# MINI-STM32.net
KiCad netlist of a schematic drawn in Altium Designer
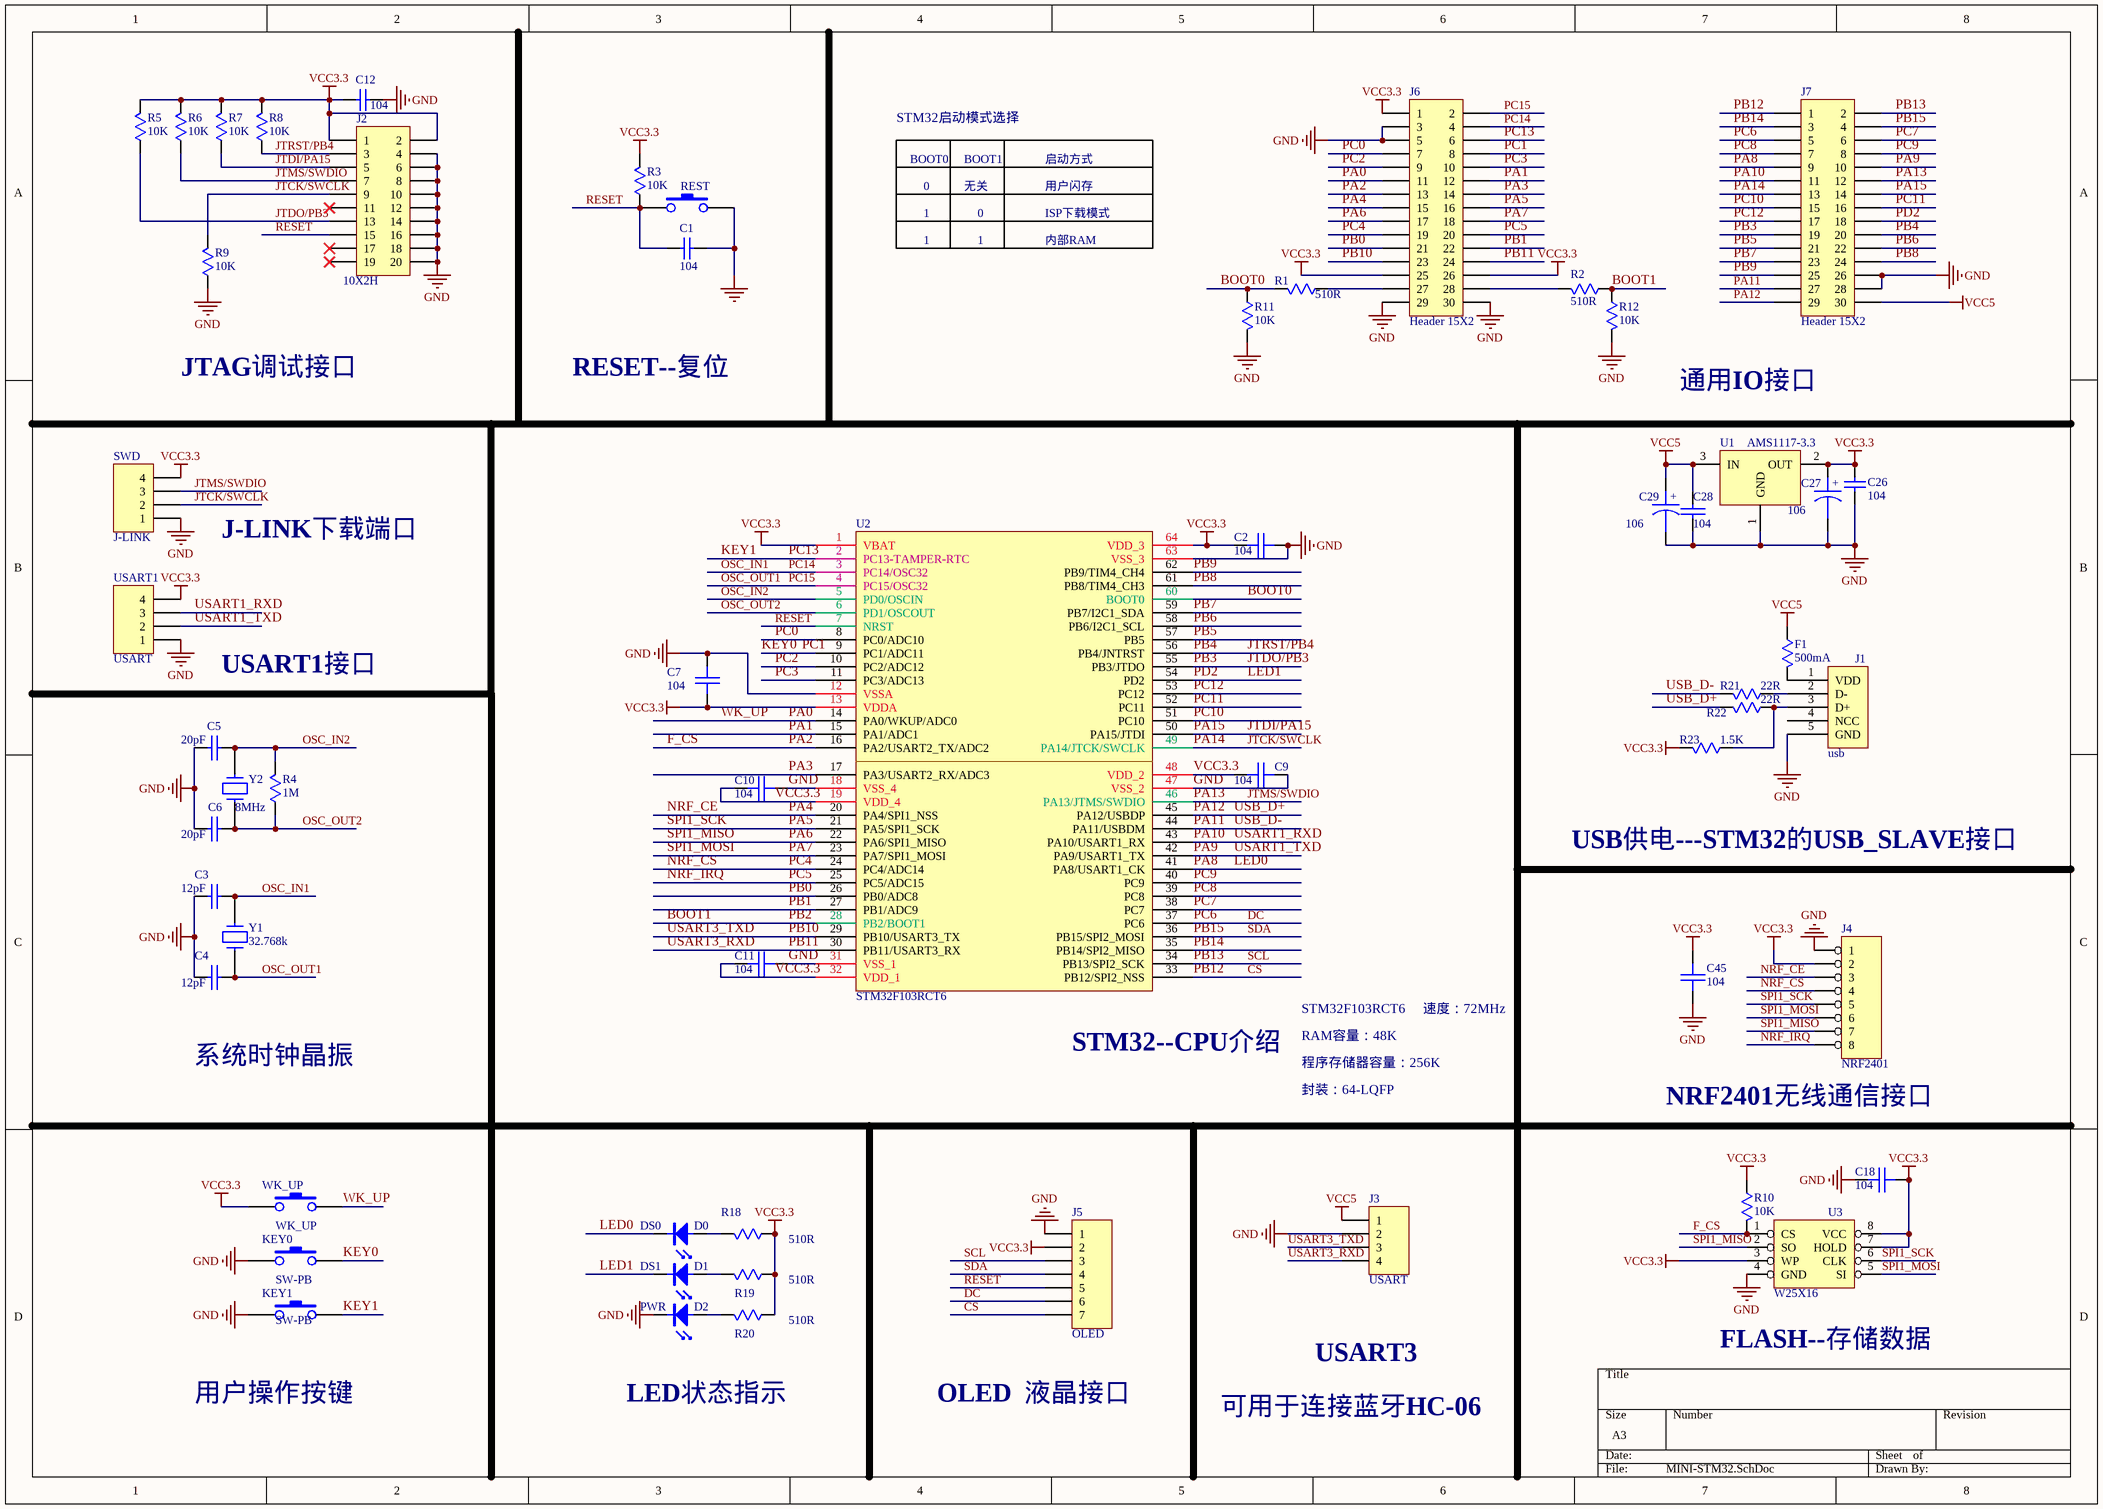
[diagram p0: MINI-STM32.SchDoc]

(export (version "E")
  (design (tool "Eeschema 10.0.6"))
  (components
    (comp (ref "C1")
      (value "104")
      (footprint "0603C")
      (description "GRM39 X7R102K50PT")
      (fields (field (name "PUBLISHER") "Altium Limited"))
      (libsource (lib "Miscellaneous Devices") (part "CAP"))
    )
    (comp (ref "C2") (value "104") (footprint "0603J") (libsource (lib "YT1_SCH_99SE") (part "CAP")))
    (comp (ref "C3")
      (value "12pF")
      (footprint "0603J")
      (description "CAP CHIP 20P 50V(+-5% C0G 0603)")
      (libsource (lib "") (part "CAP_1"))
    )
    (comp (ref "C4")
      (value "12pF")
      (footprint "0603J")
      (description "CAP CHIP 20P 50V(+-5% C0G 0603)")
      (libsource (lib "") (part "CAP_1"))
    )
    (comp (ref "C5")
      (value "20pF")
      (footprint "0603J")
      (description "CAP CHIP 20P 50V(+-5% C0G 0603)")
      (libsource (lib "") (part "CAP_1"))
    )
    (comp (ref "C6")
      (value "20pF")
      (footprint "0603J")
      (description "CAP CHIP 20P 50V(+-5% C0G 0603)")
      (libsource (lib "") (part "CAP_1"))
    )
    (comp (ref "C7") (value "104") (footprint "0603J") (libsource (lib "YT1_SCH_99SE") (part "CAP")))
    (comp (ref "C9") (value "104") (footprint "0603J") (libsource (lib "YT1_SCH_99SE") (part "CAP")))
    (comp (ref "C10") (value "104") (footprint "0603J") (libsource (lib "YT1_SCH_99SE") (part "CAP")))
    (comp (ref "C11") (value "104") (footprint "0603J") (libsource (lib "YT1_SCH_99SE") (part "CAP")))
    (comp (ref "C12")
      (value "104")
      (footprint "0603C")
      (description "GRM39 X7R102K50PT")
      (fields (field (name "PUBLISHER") "Altium Limited"))
      (libsource (lib "Miscellaneous Devices") (part "CAP"))
    )
    (comp (ref "C18") (value "104") (footprint "0603J") (libsource (lib "YT1_SCH_99SE") (part "CAP")))
    (comp (ref "C26")
      (value "104")
      (footprint "0603J")
      (description "Capacitor")
      (fields (field (name "PUBLISHER") "Altium Limited"))
      (libsource (lib "*") (part "Cap"))
    )
    (comp (ref "C27")
      (value "106")
      (footprint "TAC_3216")
      (description "Capacitor")
      (libsource (lib "*") (part "CAPACITOR POL"))
    )
    (comp (ref "C28")
      (value "104")
      (footprint "0603J")
      (description "Capacitor")
      (libsource (lib "*") (part "CAP"))
    )
    (comp (ref "C29")
      (value "106")
      (footprint "TAC_3216")
      (description "Capacitor")
      (libsource (lib "*") (part "CAPACITOR POL"))
    )
    (comp (ref "C45") (value "104") (footprint "0603J") (libsource (lib "YT1_SCH_99SE") (part "CAP")))
    (comp (ref "D0") (value "DS0") (footprint "LED_0603(B)") (libsource (lib "YT1_SCH_99SE") (part "LED")))
    (comp (ref "D1") (value "DS1") (footprint "LED_0603(B)") (libsource (lib "YT1_SCH_99SE") (part "LED")))
    (comp (ref "D2") (value "PWR") (footprint "LED_0603(B)") (libsource (lib "YT1_SCH_99SE") (part "LED")))
    (comp (ref "F1") (value "500mA") (footprint "RC0805") (libsource (lib "YT1_SCH_99SE") (part "RES")))
    (comp (ref "J1") (value "usb") (footprint "mini_USB") (libsource (lib "YT1_SCH_99SE") (part "usb")))
    (comp (ref "J2")
      (value "10X2H")
      (footprint "IDC20")
      (description "Header, 10-Pin, Dual row, Right Angle")
      (fields (field (name "PUBLISHER") "Altium Limited"))
      (libsource (lib "Miscellaneous Connectors") (part "Header 10X2H"))
    )
    (comp (ref "J3")
      (value "USART")
      (footprint "HDR1X4")
      (description "Header, 4-Pin")
      (fields (field (name "PUBLISHER") "Altium Limited"))
      (libsource (lib "") (part "Header 4_1"))
    )
    (comp (ref "J4")
      (value "NRF2401")
      (footprint "HDR2X4")
      (description "8 Pin Header")
      (libsource (lib "YT1_SCH_99SE") (part "HEADER 8"))
    )
    (comp (ref "J5")
      (value "OLED")
      (footprint "HDR1X7")
      (description "Header, 7-Pin")
      (fields (field (name "PUBLISHER") "Altium Limited"))
      (libsource (lib "Miscellaneous Connectors") (part "Header 7"))
    )
    (comp (ref "J6")
      (value "Header 15X2")
      (footprint "IDE15X2_2.54")
      (description "Header, 15-Pin, Dual row")
      (fields (field (name "PUBLISHER") "Altium Limited"))
      (libsource (lib "Miscellaneous Connectors") (part "Header 15X2"))
    )
    (comp (ref "J7")
      (value "Header 15X2")
      (footprint "IDE15X2_2.54")
      (description "Header, 15-Pin, Dual row")
      (fields (field (name "PUBLISHER") "Altium Limited"))
      (libsource (lib "Miscellaneous Connectors") (part "Header 15X2"))
    )
    (comp (ref "KEY0") (value "SW-PB") (footprint "micro button_2_SMD") (libsource (lib "*") (part "SW-PB")))
    (comp (ref "KEY1") (value "SW-PB") (footprint "micro button_2_SMD") (libsource (lib "*") (part "SW-PB")))
    (comp (ref "R1") (value "510R") (footprint "0603J") (libsource (lib "YT1_SCH_99SE") (part "RES")))
    (comp (ref "R2") (value "510R") (footprint "0603J") (libsource (lib "YT1_SCH_99SE") (part "RES")))
    (comp (ref "R3") (value "10K") (footprint "0603J") (libsource (lib "YT1_SCH_99SE") (part "RES")))
    (comp (ref "R4") (value "1M") (footprint "0603J") (libsource (lib "YT1_SCH_99SE") (part "RES")))
    (comp (ref "R5") (value "10K") (footprint "0603J") (libsource (lib "YT1_SCH_99SE") (part "RES")))
    (comp (ref "R6") (value "10K") (footprint "0603J") (libsource (lib "YT1_SCH_99SE") (part "RES")))
    (comp (ref "R7") (value "10K") (footprint "0603J") (libsource (lib "YT1_SCH_99SE") (part "RES")))
    (comp (ref "R8") (value "10K") (footprint "0603J") (libsource (lib "YT1_SCH_99SE") (part "RES")))
    (comp (ref "R9") (value "10K") (footprint "0603J") (libsource (lib "YT1_SCH_99SE") (part "RES")))
    (comp (ref "R10") (value "10K") (footprint "0603J") (libsource (lib "YT1_SCH_99SE") (part "RES")))
    (comp (ref "R11") (value "10K") (footprint "0603J") (libsource (lib "YT1_SCH_99SE") (part "RES")))
    (comp (ref "R12") (value "10K") (footprint "0603J") (libsource (lib "YT1_SCH_99SE") (part "RES")))
    (comp (ref "R18") (value "510R") (footprint "0603J") (libsource (lib "YT1_SCH_99SE") (part "RES")))
    (comp (ref "R19") (value "510R") (footprint "0603J") (libsource (lib "YT1_SCH_99SE") (part "RES")))
    (comp (ref "R20") (value "510R") (footprint "0603J") (libsource (lib "YT1_SCH_99SE") (part "RES")))
    (comp (ref "R21") (value "22R") (footprint "0603J") (libsource (lib "YT1_SCH_99SE") (part "RES")))
    (comp (ref "R22") (value "22R") (footprint "0603J") (libsource (lib "YT1_SCH_99SE") (part "RES")))
    (comp (ref "R23") (value "1.5K") (footprint "0603J") (libsource (lib "YT1_SCH_99SE") (part "RES")))
    (comp (ref "REST") (value "~") (footprint "micro button_2_SMD") (libsource (lib "*") (part "SW-PB")))
    (comp (ref "SWD")
      (value "J-LINK")
      (footprint "HDR1X4")
      (description "Header, 4-Pin")
      (fields (field (name "PUBLISHER") "Altium Limited"))
      (libsource (lib "Miscellaneous Connectors") (part "Header 4"))
    )
    (comp (ref "U1")
      (value "AMS1117-3.3")
      (footprint "SOT223")
      (libsource (lib "Newcapec9263_Board_NEW") (part "LT1085CM-3.3"))
    )
    (comp (ref "U2")
      (value "STM32F103RCT6")
      (footprint "LQFP64")
      (libsource (lib "YT1_SCH_99SE") (part "STM32F103RBT6"))
    )
    (comp (ref "U3") (value "W25X16") (footprint "SOIC8P") (libsource (lib "YT1_SCH_99SE") (part "W25X16")))
    (comp (ref "USART1")
      (value "USART")
      (footprint "HDR1X4")
      (description "Header, 4-Pin")
      (fields (field (name "PUBLISHER") "Altium Limited"))
      (libsource (lib "Miscellaneous Connectors") (part "Header 4"))
    )
    (comp (ref "WK_UP") (value "WK_UP") (footprint "micro button_2_SMD") (libsource (lib "*") (part "SW-PB")))
    (comp (ref "Y1")
      (value "32.768k")
      (footprint "32.768k")
      (description "Crystal 8MHz PLUG")
      (libsource (lib "*") (part "CRYSTAL"))
    )
    (comp (ref "Y2")
      (value "8MHz")
      (footprint "smt-xtal")
      (description "Crystal 8MHz PLUG")
      (libsource (lib "*") (part "CRYSTAL"))
    )
  )
  (nets
    (net (code "1") (name "/BOOT0") (class "Default")
      (node (ref "R1") (pin "2") (pinfunction "2_2") (pintype "passive"))
      (node (ref "R11") (pin "1") (pinfunction "1_1") (pintype "passive"))
      (node (ref "U2") (pin "60") (pinfunction "BOOT0_60") (pintype "passive"))
    )
    (net (code "2") (name "/BOOT1") (class "Default")
      (node (ref "R12") (pin "1") (pinfunction "1_1") (pintype "passive"))
      (node (ref "R2") (pin "1") (pinfunction "1_1") (pintype "passive"))
      (node (ref "U2") (pin "28") (pinfunction "PB2/BOOT1_28") (pintype "passive"))
    )
    (net (code "3") (name "/CS") (class "Default")
      (node (ref "J5") (pin "7") (pinfunction "7_7") (pintype "passive"))
      (node (ref "J7") (pin "1") (pinfunction "1_1") (pintype "passive"))
      (node (ref "U2") (pin "33") (pinfunction "PB12/SPI2_NSS_33") (pintype "passive"))
    )
    (net (code "4") (name "/DC") (class "Default")
      (node (ref "J5") (pin "6") (pinfunction "6_6") (pintype "passive"))
      (node (ref "J7") (pin "5") (pinfunction "5_5") (pintype "passive"))
      (node (ref "U2") (pin "37") (pinfunction "PC6_37") (pintype "passive"))
    )
    (net (code "5") (name "/F_CS") (class "Default")
      (node (ref "J6") (pin "13") (pinfunction "13_13") (pintype "passive"))
      (node (ref "R10") (pin "2") (pinfunction "2_2") (pintype "passive"))
      (node (ref "U2") (pin "16") (pinfunction "PA2/USART2_TX/ADC2_16") (pintype "passive"))
      (node (ref "U3") (pin "1") (pinfunction "CS_1") (pintype "passive"))
    )
    (net (code "6") (name "/JTCK{slash}SWCLK") (class "Default")
      (node (ref "J2") (pin "9") (pinfunction "9_9") (pintype "passive"))
      (node (ref "J7") (pin "13") (pinfunction "13_13") (pintype "passive"))
      (node (ref "R9") (pin "2") (pinfunction "2_2") (pintype "passive"))
      (node (ref "SWD") (pin "2") (pinfunction "2_2") (pintype "passive"))
      (node (ref "U2") (pin "49") (pinfunction "PA14/JTCK/SWCLK_49") (pintype "passive"))
    )
    (net (code "7") (name "/JTDI{slash}PA15") (class "Default")
      (node (ref "J2") (pin "5") (pinfunction "5_5") (pintype "passive"))
      (node (ref "J7") (pin "14") (pinfunction "14_14") (pintype "passive"))
      (node (ref "R7") (pin "1") (pinfunction "1_1") (pintype "passive"))
      (node (ref "U2") (pin "50") (pinfunction "PA15/JTDI_50") (pintype "passive"))
    )
    (net (code "8") (name "/JTDO{slash}PB3") (class "Default")
      (node (ref "J2") (pin "13") (pinfunction "13_13") (pintype "passive"))
      (node (ref "J7") (pin "19") (pinfunction "19_19") (pintype "passive"))
      (node (ref "R5") (pin "1") (pinfunction "1_1") (pintype "passive"))
      (node (ref "U2") (pin "55") (pinfunction "PB3/JTDO_55") (pintype "passive"))
    )
    (net (code "9") (name "/JTMS{slash}SWDIO") (class "Default")
      (node (ref "J2") (pin "7") (pinfunction "7_7") (pintype "passive"))
      (node (ref "J7") (pin "12") (pinfunction "12_12") (pintype "passive"))
      (node (ref "R6") (pin "1") (pinfunction "1_1") (pintype "passive"))
      (node (ref "SWD") (pin "3") (pinfunction "3_3") (pintype "passive"))
      (node (ref "U2") (pin "46") (pinfunction "PA13/JTMS/SWDIO_46") (pintype "passive"))
    )
    (net (code "10") (name "/JTRST{slash}PB4") (class "Default")
      (node (ref "J2") (pin "3") (pinfunction "3_3") (pintype "passive"))
      (node (ref "J7") (pin "20") (pinfunction "20_20") (pintype "passive"))
      (node (ref "R8") (pin "1") (pinfunction "1_1") (pintype "passive"))
      (node (ref "U2") (pin "56") (pinfunction "PB4/JNTRST_56") (pintype "passive"))
    )
    (net (code "11") (name "/KEY0") (class "Default")
      (node (ref "J6") (pin "8") (pinfunction "8_8") (pintype "passive"))
      (node (ref "KEY0") (pin "2") (pinfunction "2_2") (pintype "passive"))
      (node (ref "U2") (pin "9") (pinfunction "PC1/ADC11_9") (pintype "passive"))
    )
    (net (code "12") (name "/KEY1") (class "Default")
      (node (ref "J6") (pin "6") (pinfunction "6_6") (pintype "passive"))
      (node (ref "KEY1") (pin "2") (pinfunction "2_2") (pintype "passive"))
      (node (ref "U2") (pin "2") (pinfunction "PC13-TAMPER-RTC_2") (pintype "passive"))
    )
    (net (code "13") (name "/LED0") (class "Default")
      (node (ref "D0") (pin "2") (pinfunction "2_2") (pintype "passive"))
      (node (ref "J7") (pin "9") (pinfunction "9_9") (pintype "passive"))
      (node (ref "U2") (pin "41") (pinfunction "PA8/USART1_CK_41") (pintype "passive"))
    )
    (net (code "14") (name "/LED1") (class "Default")
      (node (ref "D1") (pin "2") (pinfunction "2_2") (pintype "passive"))
      (node (ref "J7") (pin "18") (pinfunction "18_18") (pintype "passive"))
      (node (ref "U2") (pin "54") (pinfunction "PD2_54") (pintype "passive"))
    )
    (net (code "15") (name "/NRF_CE") (class "Default")
      (node (ref "J4") (pin "3") (pinfunction "3_3") (pintype "passive"))
      (node (ref "J6") (pin "15") (pinfunction "15_15") (pintype "passive"))
      (node (ref "U2") (pin "20") (pinfunction "PA4/SPI1_NSS_20") (pintype "passive"))
    )
    (net (code "16") (name "/NRF_CS") (class "Default")
      (node (ref "J4") (pin "4") (pinfunction "4_4") (pintype "passive"))
      (node (ref "J6") (pin "19") (pinfunction "19_19") (pintype "passive"))
      (node (ref "U2") (pin "24") (pinfunction "PC4/ADC14_24") (pintype "passive"))
    )
    (net (code "17") (name "/NRF_IRQ") (class "Default")
      (node (ref "J4") (pin "8") (pinfunction "8_8") (pintype "passive"))
      (node (ref "J6") (pin "20") (pinfunction "20_20") (pintype "passive"))
      (node (ref "U2") (pin "25") (pinfunction "PC5/ADC15_25") (pintype "passive"))
    )
    (net (code "18") (name "/OSC_IN1") (class "Default")
      (node (ref "C3") (pin "2") (pinfunction "2_2") (pintype "passive"))
      (node (ref "J6") (pin "4") (pinfunction "4_4") (pintype "passive"))
      (node (ref "U2") (pin "3") (pinfunction "PC14/OSC32_3") (pintype "passive"))
      (node (ref "Y1") (pin "2") (pinfunction "2_2") (pintype "passive"))
    )
    (net (code "19") (name "/OSC_IN2") (class "Default")
      (node (ref "C5") (pin "2") (pinfunction "2_2") (pintype "passive"))
      (node (ref "R4") (pin "2") (pinfunction "2_2") (pintype "passive"))
      (node (ref "U2") (pin "5") (pinfunction "PD0/OSCIN_5") (pintype "passive"))
      (node (ref "Y2") (pin "1") (pinfunction "1_1") (pintype "passive"))
    )
    (net (code "20") (name "/OSC_OUT1") (class "Default")
      (node (ref "C4") (pin "2") (pinfunction "2_2") (pintype "passive"))
      (node (ref "J6") (pin "2") (pinfunction "2_2") (pintype "passive"))
      (node (ref "U2") (pin "4") (pinfunction "PC15/OSC32_4") (pintype "passive"))
      (node (ref "Y1") (pin "1") (pinfunction "1_1") (pintype "passive"))
    )
    (net (code "21") (name "/OSC_OUT2") (class "Default")
      (node (ref "C6") (pin "2") (pinfunction "2_2") (pintype "passive"))
      (node (ref "R4") (pin "1") (pinfunction "1_1") (pintype "passive"))
      (node (ref "U2") (pin "6") (pinfunction "PD1/OSCOUT_6") (pintype "passive"))
      (node (ref "Y2") (pin "2") (pinfunction "2_2") (pintype "passive"))
    )
    (net (code "22") (name "/PA0") (class "Default")
      (node (ref "J6") (pin "11") (pinfunction "11_11") (pintype "passive"))
      (node (ref "U2") (pin "14") (pinfunction "PA0/WKUP/ADC0_14") (pintype "passive"))
      (node (ref "WK_UP") (pin "2") (pinfunction "2_2") (pintype "passive"))
    )
    (net (code "23") (name "/PA1") (class "Default")
      (node (ref "J6") (pin "12") (pinfunction "12_12") (pintype "passive"))
      (node (ref "U2") (pin "15") (pinfunction "PA1/ADC1_15") (pintype "passive"))
    )
    (net (code "24") (name "/PA3") (class "Default")
      (node (ref "J6") (pin "14") (pinfunction "14_14") (pintype "passive"))
      (node (ref "U2") (pin "17") (pinfunction "PA3/USART2_RX/ADC3_17") (pintype "passive"))
    )
    (net (code "25") (name "/PA5") (class "Default")
      (node (ref "J4") (pin "5") (pinfunction "5_5") (pintype "passive"))
      (node (ref "J6") (pin "16") (pinfunction "16_16") (pintype "passive"))
      (node (ref "U2") (pin "21") (pinfunction "PA5/SPI1_SCK_21") (pintype "passive"))
      (node (ref "U3") (pin "6") (pinfunction "CLK_6") (pintype "passive"))
    )
    (net (code "26") (name "/PA6") (class "Default")
      (node (ref "J4") (pin "7") (pinfunction "7_7") (pintype "passive"))
      (node (ref "J6") (pin "17") (pinfunction "17_17") (pintype "passive"))
      (node (ref "U2") (pin "22") (pinfunction "PA6/SPI1_MISO_22") (pintype "passive"))
      (node (ref "U3") (pin "2") (pinfunction "SO_2") (pintype "passive"))
    )
    (net (code "27") (name "/PA7") (class "Default")
      (node (ref "J4") (pin "6") (pinfunction "6_6") (pintype "passive"))
      (node (ref "J6") (pin "18") (pinfunction "18_18") (pintype "passive"))
      (node (ref "U2") (pin "23") (pinfunction "PA7/SPI1_MOSI_23") (pintype "passive"))
      (node (ref "U3") (pin "5") (pinfunction "SI_5") (pintype "passive"))
    )
    (net (code "28") (name "/PA9") (class "Default")
      (node (ref "J7") (pin "10") (pinfunction "10_10") (pintype "passive"))
      (node (ref "U2") (pin "42") (pinfunction "PA9/USART1_TX_42") (pintype "passive"))
      (node (ref "USART1") (pin "2") (pinfunction "2_2") (pintype "passive"))
    )
    (net (code "29") (name "/PA10") (class "Default")
      (node (ref "J7") (pin "11") (pinfunction "11_11") (pintype "passive"))
      (node (ref "U2") (pin "43") (pinfunction "PA10/USART1_RX_43") (pintype "passive"))
      (node (ref "USART1") (pin "3") (pinfunction "3_3") (pintype "passive"))
    )
    (net (code "30") (name "/PA11") (class "Default")
      (node (ref "J7") (pin "27") (pinfunction "27_27") (pintype "passive"))
      (node (ref "R21") (pin "2") (pinfunction "2_2") (pintype "passive"))
      (node (ref "U2") (pin "44") (pinfunction "PA11/USBDM_44") (pintype "passive"))
    )
    (net (code "31") (name "/PA12") (class "Default")
      (node (ref "J7") (pin "29") (pinfunction "29_29") (pintype "passive"))
      (node (ref "R22") (pin "2") (pinfunction "2_2") (pintype "passive"))
      (node (ref "U2") (pin "45") (pinfunction "PA12/USBDP_45") (pintype "passive"))
    )
    (net (code "32") (name "/PB0") (class "Default")
      (node (ref "J6") (pin "21") (pinfunction "21_21") (pintype "passive"))
      (node (ref "U2") (pin "26") (pinfunction "PB0/ADC8_26") (pintype "passive"))
    )
    (net (code "33") (name "/PB1") (class "Default")
      (node (ref "J6") (pin "22") (pinfunction "22_22") (pintype "passive"))
      (node (ref "U2") (pin "27") (pinfunction "PB1/ADC9_27") (pintype "passive"))
    )
    (net (code "34") (name "/PB5") (class "Default")
      (node (ref "J7") (pin "21") (pinfunction "21_21") (pintype "passive"))
      (node (ref "U2") (pin "57") (pinfunction "PB5_57") (pintype "passive"))
    )
    (net (code "35") (name "/PB6") (class "Default")
      (node (ref "J7") (pin "22") (pinfunction "22_22") (pintype "passive"))
      (node (ref "U2") (pin "58") (pinfunction "PB6/I2C1_SCL_58") (pintype "passive"))
    )
    (net (code "36") (name "/PB7") (class "Default")
      (node (ref "J7") (pin "23") (pinfunction "23_23") (pintype "passive"))
      (node (ref "U2") (pin "59") (pinfunction "PB7/I2C1_SDA_59") (pintype "passive"))
    )
    (net (code "37") (name "/PB8") (class "Default")
      (node (ref "J7") (pin "24") (pinfunction "24_24") (pintype "passive"))
      (node (ref "U2") (pin "61") (pinfunction "PB8/TIM4_CH3_61") (pintype "passive"))
    )
    (net (code "38") (name "/PB9") (class "Default")
      (node (ref "J7") (pin "25") (pinfunction "25_25") (pintype "passive"))
      (node (ref "U2") (pin "62") (pinfunction "PB9/TIM4_CH4_62") (pintype "passive"))
    )
    (net (code "39") (name "/PB10") (class "Default")
      (node (ref "J3") (pin "3") (pinfunction "3_3") (pintype "passive"))
      (node (ref "J6") (pin "23") (pinfunction "23_23") (pintype "passive"))
      (node (ref "U2") (pin "29") (pinfunction "PB10/USART3_TX_29") (pintype "passive"))
    )
    (net (code "40") (name "/PB11") (class "Default")
      (node (ref "J3") (pin "4") (pinfunction "4_4") (pintype "passive"))
      (node (ref "J6") (pin "24") (pinfunction "24_24") (pintype "passive"))
      (node (ref "U2") (pin "30") (pinfunction "PB11/USART3_RX_30") (pintype "passive"))
    )
    (net (code "41") (name "/PB13") (class "Default")
      (node (ref "J5") (pin "3") (pinfunction "3_3") (pintype "passive"))
      (node (ref "J7") (pin "2") (pinfunction "2_2") (pintype "passive"))
      (node (ref "U2") (pin "34") (pinfunction "PB13/SPI2_SCK_34") (pintype "passive"))
    )
    (net (code "42") (name "/PB14") (class "Default")
      (node (ref "J7") (pin "3") (pinfunction "3_3") (pintype "passive"))
      (node (ref "U2") (pin "35") (pinfunction "PB14/SPI2_MISO_35") (pintype "passive"))
    )
    (net (code "43") (name "/PB15") (class "Default")
      (node (ref "J5") (pin "4") (pinfunction "4_4") (pintype "passive"))
      (node (ref "J7") (pin "4") (pinfunction "4_4") (pintype "passive"))
      (node (ref "U2") (pin "36") (pinfunction "PB15/SPI2_MOSI_36") (pintype "passive"))
    )
    (net (code "44") (name "/PC0") (class "Default")
      (node (ref "J6") (pin "7") (pinfunction "7_7") (pintype "passive"))
      (node (ref "U2") (pin "8") (pinfunction "PC0/ADC10_8") (pintype "passive"))
    )
    (net (code "45") (name "/PC2") (class "Default")
      (node (ref "J6") (pin "9") (pinfunction "9_9") (pintype "passive"))
      (node (ref "U2") (pin "10") (pinfunction "PC2/ADC12_10") (pintype "passive"))
    )
    (net (code "46") (name "/PC3") (class "Default")
      (node (ref "J6") (pin "10") (pinfunction "10_10") (pintype "passive"))
      (node (ref "U2") (pin "11") (pinfunction "PC3/ADC13_11") (pintype "passive"))
    )
    (net (code "47") (name "/PC7") (class "Default")
      (node (ref "J7") (pin "6") (pinfunction "6_6") (pintype "passive"))
      (node (ref "U2") (pin "38") (pinfunction "PC7_38") (pintype "passive"))
    )
    (net (code "48") (name "/PC8") (class "Default")
      (node (ref "J7") (pin "7") (pinfunction "7_7") (pintype "passive"))
      (node (ref "U2") (pin "39") (pinfunction "PC8_39") (pintype "passive"))
    )
    (net (code "49") (name "/PC9") (class "Default")
      (node (ref "J7") (pin "8") (pinfunction "8_8") (pintype "passive"))
      (node (ref "U2") (pin "40") (pinfunction "PC9_40") (pintype "passive"))
    )
    (net (code "50") (name "/PC10") (class "Default")
      (node (ref "J7") (pin "15") (pinfunction "15_15") (pintype "passive"))
      (node (ref "U2") (pin "51") (pinfunction "PC10_51") (pintype "passive"))
    )
    (net (code "51") (name "/PC11") (class "Default")
      (node (ref "J7") (pin "16") (pinfunction "16_16") (pintype "passive"))
      (node (ref "U2") (pin "52") (pinfunction "PC11_52") (pintype "passive"))
    )
    (net (code "52") (name "/PC12") (class "Default")
      (node (ref "J7") (pin "17") (pinfunction "17_17") (pintype "passive"))
      (node (ref "U2") (pin "53") (pinfunction "PC12_53") (pintype "passive"))
    )
    (net (code "53") (name "/RESET") (class "Default")
      (node (ref "C1") (pin "2") (pinfunction "2_2") (pintype "passive"))
      (node (ref "J2") (pin "15") (pinfunction "15_15") (pintype "passive"))
      (node (ref "J5") (pin "5") (pinfunction "5_5") (pintype "passive"))
      (node (ref "R3") (pin "1") (pinfunction "1_1") (pintype "passive"))
      (node (ref "REST") (pin "1") (pinfunction "1_1") (pintype "passive"))
      (node (ref "U2") (pin "7") (pinfunction "NRST_7") (pintype "passive"))
    )
    (net (code "54") (name "GND") (class "Default")
      (node (ref "C1") (pin "1") (pinfunction "1_1") (pintype "passive"))
      (node (ref "C10") (pin "2") (pinfunction "2_2") (pintype "passive"))
      (node (ref "C11") (pin "2") (pinfunction "2_2") (pintype "passive"))
      (node (ref "C12") (pin "2") (pinfunction "2_2") (pintype "passive"))
      (node (ref "C18") (pin "1") (pinfunction "1_1") (pintype "passive"))
      (node (ref "C2") (pin "2") (pinfunction "2_2") (pintype "passive"))
      (node (ref "C26") (pin "2") (pinfunction "2_2") (pintype "passive"))
      (node (ref "C27") (pin "2") (pinfunction "2_2") (pintype "passive"))
      (node (ref "C28") (pin "2") (pinfunction "2_2") (pintype "passive"))
      (node (ref "C29") (pin "2") (pinfunction "2_2") (pintype "passive"))
      (node (ref "C3") (pin "1") (pinfunction "1_1") (pintype "passive"))
      (node (ref "C4") (pin "1") (pinfunction "1_1") (pintype "passive"))
      (node (ref "C45") (pin "2") (pinfunction "2_2") (pintype "passive"))
      (node (ref "C5") (pin "1") (pinfunction "1_1") (pintype "passive"))
      (node (ref "C6") (pin "1") (pinfunction "1_1") (pintype "passive"))
      (node (ref "C7") (pin "1") (pinfunction "1_1") (pintype "passive"))
      (node (ref "C9") (pin "2") (pinfunction "2_2") (pintype "passive"))
      (node (ref "D2") (pin "2") (pinfunction "2_2") (pintype "passive"))
      (node (ref "J1") (pin "5") (pinfunction "GND_5") (pintype "passive"))
      (node (ref "J2") (pin "10") (pinfunction "10_10") (pintype "passive"))
      (node (ref "J2") (pin "12") (pinfunction "12_12") (pintype "passive"))
      (node (ref "J2") (pin "14") (pinfunction "14_14") (pintype "passive"))
      (node (ref "J2") (pin "16") (pinfunction "16_16") (pintype "passive"))
      (node (ref "J2") (pin "18") (pinfunction "18_18") (pintype "passive"))
      (node (ref "J2") (pin "20") (pinfunction "20_20") (pintype "passive"))
      (node (ref "J2") (pin "4") (pinfunction "4_4") (pintype "passive"))
      (node (ref "J2") (pin "6") (pinfunction "6_6") (pintype "passive"))
      (node (ref "J2") (pin "8") (pinfunction "8_8") (pintype "passive"))
      (node (ref "J3") (pin "2") (pinfunction "2_2") (pintype "passive"))
      (node (ref "J4") (pin "1") (pinfunction "1_1") (pintype "passive"))
      (node (ref "J5") (pin "1") (pinfunction "1_1") (pintype "passive"))
      (node (ref "J6") (pin "29") (pinfunction "29_29") (pintype "passive"))
      (node (ref "J6") (pin "3") (pinfunction "3_3") (pintype "passive"))
      (node (ref "J6") (pin "30") (pinfunction "30_30") (pintype "passive"))
      (node (ref "J6") (pin "5") (pinfunction "5_5") (pintype "passive"))
      (node (ref "J7") (pin "26") (pinfunction "26_26") (pintype "passive"))
      (node (ref "J7") (pin "28") (pinfunction "28_28") (pintype "passive"))
      (node (ref "KEY0") (pin "1") (pinfunction "1_1") (pintype "passive"))
      (node (ref "KEY1") (pin "1") (pinfunction "1_1") (pintype "passive"))
      (node (ref "R11") (pin "2") (pinfunction "2_2") (pintype "passive"))
      (node (ref "R12") (pin "2") (pinfunction "2_2") (pintype "passive"))
      (node (ref "R9") (pin "1") (pinfunction "1_1") (pintype "passive"))
      (node (ref "REST") (pin "2") (pinfunction "2_2") (pintype "passive"))
      (node (ref "SWD") (pin "1") (pinfunction "1_1") (pintype "passive"))
      (node (ref "U1") (pin "1") (pinfunction "GND_1") (pintype "passive"))
      (node (ref "U2") (pin "12") (pinfunction "VSSA_12") (pintype "passive"))
      (node (ref "U2") (pin "18") (pinfunction "VSS_4_18") (pintype "passive"))
      (node (ref "U2") (pin "31") (pinfunction "VSS_1_31") (pintype "passive"))
      (node (ref "U2") (pin "47") (pinfunction "VSS_2_47") (pintype "passive"))
      (node (ref "U2") (pin "63") (pinfunction "VSS_3_63") (pintype "passive"))
      (node (ref "U3") (pin "4") (pinfunction "GND_4") (pintype "passive"))
      (node (ref "USART1") (pin "1") (pinfunction "1_1") (pintype "passive"))
    )
    (net (code "55") (name "Net-(D0-Pad1)") (class "Default")
      (node (ref "D0") (pin "1") (pinfunction "1_1") (pintype "passive"))
      (node (ref "R18") (pin "2") (pinfunction "2_2") (pintype "passive"))
    )
    (net (code "56") (name "Net-(D1-Pad1)") (class "Default")
      (node (ref "D1") (pin "1") (pinfunction "1_1") (pintype "passive"))
      (node (ref "R19") (pin "2") (pinfunction "2_2") (pintype "passive"))
    )
    (net (code "57") (name "Net-(D2-Pad1)") (class "Default")
      (node (ref "D2") (pin "1") (pinfunction "1_1") (pintype "passive"))
      (node (ref "R20") (pin "2") (pinfunction "2_2") (pintype "passive"))
    )
    (net (code "58") (name "Net-(J1-D+)") (class "Default")
      (node (ref "J1") (pin "3") (pinfunction "D+_3") (pintype "passive"))
      (node (ref "R22") (pin "1") (pinfunction "1_1") (pintype "passive"))
      (node (ref "R23") (pin "1") (pinfunction "1_1") (pintype "passive"))
    )
    (net (code "59") (name "Net-(J1-D-)") (class "Default")
      (node (ref "J1") (pin "2") (pinfunction "D-_2") (pintype "passive"))
      (node (ref "R21") (pin "1") (pinfunction "1_1") (pintype "passive"))
    )
    (net (code "60") (name "Net-(J1-VDD)") (class "Default")
      (node (ref "F1") (pin "2") (pinfunction "2_2") (pintype "passive"))
      (node (ref "J1") (pin "1") (pinfunction "VDD_1") (pintype "passive"))
    )
    (net (code "61") (name "Net-(J6-Pad27)") (class "Default")
      (node (ref "J6") (pin "27") (pinfunction "27_27") (pintype "passive"))
      (node (ref "R1") (pin "1") (pinfunction "1_1") (pintype "passive"))
    )
    (net (code "62") (name "Net-(J6-Pad28)") (class "Default")
      (node (ref "J6") (pin "28") (pinfunction "28_28") (pintype "passive"))
      (node (ref "R2") (pin "2") (pinfunction "2_2") (pintype "passive"))
    )
    (net (code "63") (name "VCC3.3") (class "Default")
      (node (ref "C10") (pin "1") (pinfunction "1_1") (pintype "passive"))
      (node (ref "C11") (pin "1") (pinfunction "1_1") (pintype "passive"))
      (node (ref "C12") (pin "1") (pinfunction "1_1") (pintype "passive"))
      (node (ref "C18") (pin "2") (pinfunction "2_2") (pintype "passive"))
      (node (ref "C2") (pin "1") (pinfunction "1_1") (pintype "passive"))
      (node (ref "C26") (pin "1") (pinfunction "1_1") (pintype "passive"))
      (node (ref "C27") (pin "1") (pinfunction "1_1") (pintype "passive"))
      (node (ref "C45") (pin "1") (pinfunction "1_1") (pintype "passive"))
      (node (ref "C7") (pin "2") (pinfunction "2_2") (pintype "passive"))
      (node (ref "C9") (pin "1") (pinfunction "1_1") (pintype "passive"))
      (node (ref "J2") (pin "1") (pinfunction "1_1") (pintype "passive"))
      (node (ref "J2") (pin "2") (pinfunction "2_2") (pintype "passive"))
      (node (ref "J4") (pin "2") (pinfunction "2_2") (pintype "passive"))
      (node (ref "J5") (pin "2") (pinfunction "2_2") (pintype "passive"))
      (node (ref "J6") (pin "1") (pinfunction "1_1") (pintype "passive"))
      (node (ref "J6") (pin "25") (pinfunction "25_25") (pintype "passive"))
      (node (ref "J6") (pin "26") (pinfunction "26_26") (pintype "passive"))
      (node (ref "R10") (pin "1") (pinfunction "1_1") (pintype "passive"))
      (node (ref "R18") (pin "1") (pinfunction "1_1") (pintype "passive"))
      (node (ref "R19") (pin "1") (pinfunction "1_1") (pintype "passive"))
      (node (ref "R20") (pin "1") (pinfunction "1_1") (pintype "passive"))
      (node (ref "R23") (pin "2") (pinfunction "2_2") (pintype "passive"))
      (node (ref "R3") (pin "2") (pinfunction "2_2") (pintype "passive"))
      (node (ref "R5") (pin "2") (pinfunction "2_2") (pintype "passive"))
      (node (ref "R6") (pin "2") (pinfunction "2_2") (pintype "passive"))
      (node (ref "R7") (pin "2") (pinfunction "2_2") (pintype "passive"))
      (node (ref "R8") (pin "2") (pinfunction "2_2") (pintype "passive"))
      (node (ref "SWD") (pin "4") (pinfunction "4_4") (pintype "passive"))
      (node (ref "U1") (pin "2") (pinfunction "OUT_2") (pintype "passive"))
      (node (ref "U2") (pin "1") (pinfunction "VBAT_1") (pintype "passive"))
      (node (ref "U2") (pin "13") (pinfunction "VDDA_13") (pintype "passive"))
      (node (ref "U2") (pin "19") (pinfunction "VDD_4_19") (pintype "passive"))
      (node (ref "U2") (pin "32") (pinfunction "VDD_1_32") (pintype "passive"))
      (node (ref "U2") (pin "48") (pinfunction "VDD_2_48") (pintype "passive"))
      (node (ref "U2") (pin "64") (pinfunction "VDD_3_64") (pintype "passive"))
      (node (ref "U3") (pin "3") (pinfunction "WP_3") (pintype "passive"))
      (node (ref "U3") (pin "7") (pinfunction "HOLD_7") (pintype "passive"))
      (node (ref "U3") (pin "8") (pinfunction "VCC_8") (pintype "passive"))
      (node (ref "USART1") (pin "4") (pinfunction "4_4") (pintype "passive"))
      (node (ref "WK_UP") (pin "1") (pinfunction "1_1") (pintype "passive"))
    )
    (net (code "64") (name "VCC5") (class "Default")
      (node (ref "C28") (pin "1") (pinfunction "1_1") (pintype "passive"))
      (node (ref "C29") (pin "1") (pinfunction "1_1") (pintype "passive"))
      (node (ref "F1") (pin "1") (pinfunction "1_1") (pintype "passive"))
      (node (ref "J3") (pin "1") (pinfunction "1_1") (pintype "passive"))
      (node (ref "J7") (pin "30") (pinfunction "30_30") (pintype "passive"))
      (node (ref "U1") (pin "3") (pinfunction "IN_3") (pintype "passive"))
    )
    (net (code "65") (name "unconnected-(J1-NCC-Pad4)") (class "Default")
      (node (ref "J1") (pin "4") (pinfunction "NCC_4") (pintype "passive"))
    )
    (net (code "66") (name "unconnected-(J2-Pad11)") (class "Default")
      (node (ref "J2") (pin "11") (pinfunction "11_11") (pintype "passive+no_connect"))
    )
    (net (code "67") (name "unconnected-(J2-Pad17)") (class "Default")
      (node (ref "J2") (pin "17") (pinfunction "17_17") (pintype "passive+no_connect"))
    )
    (net (code "68") (name "unconnected-(J2-Pad19)") (class "Default")
      (node (ref "J2") (pin "19") (pinfunction "19_19") (pintype "passive+no_connect"))
    )
  )
)
